# 1-Schematic_LED_PISCA.net
KiCad netlist of a schematic drawn in EasyEDA
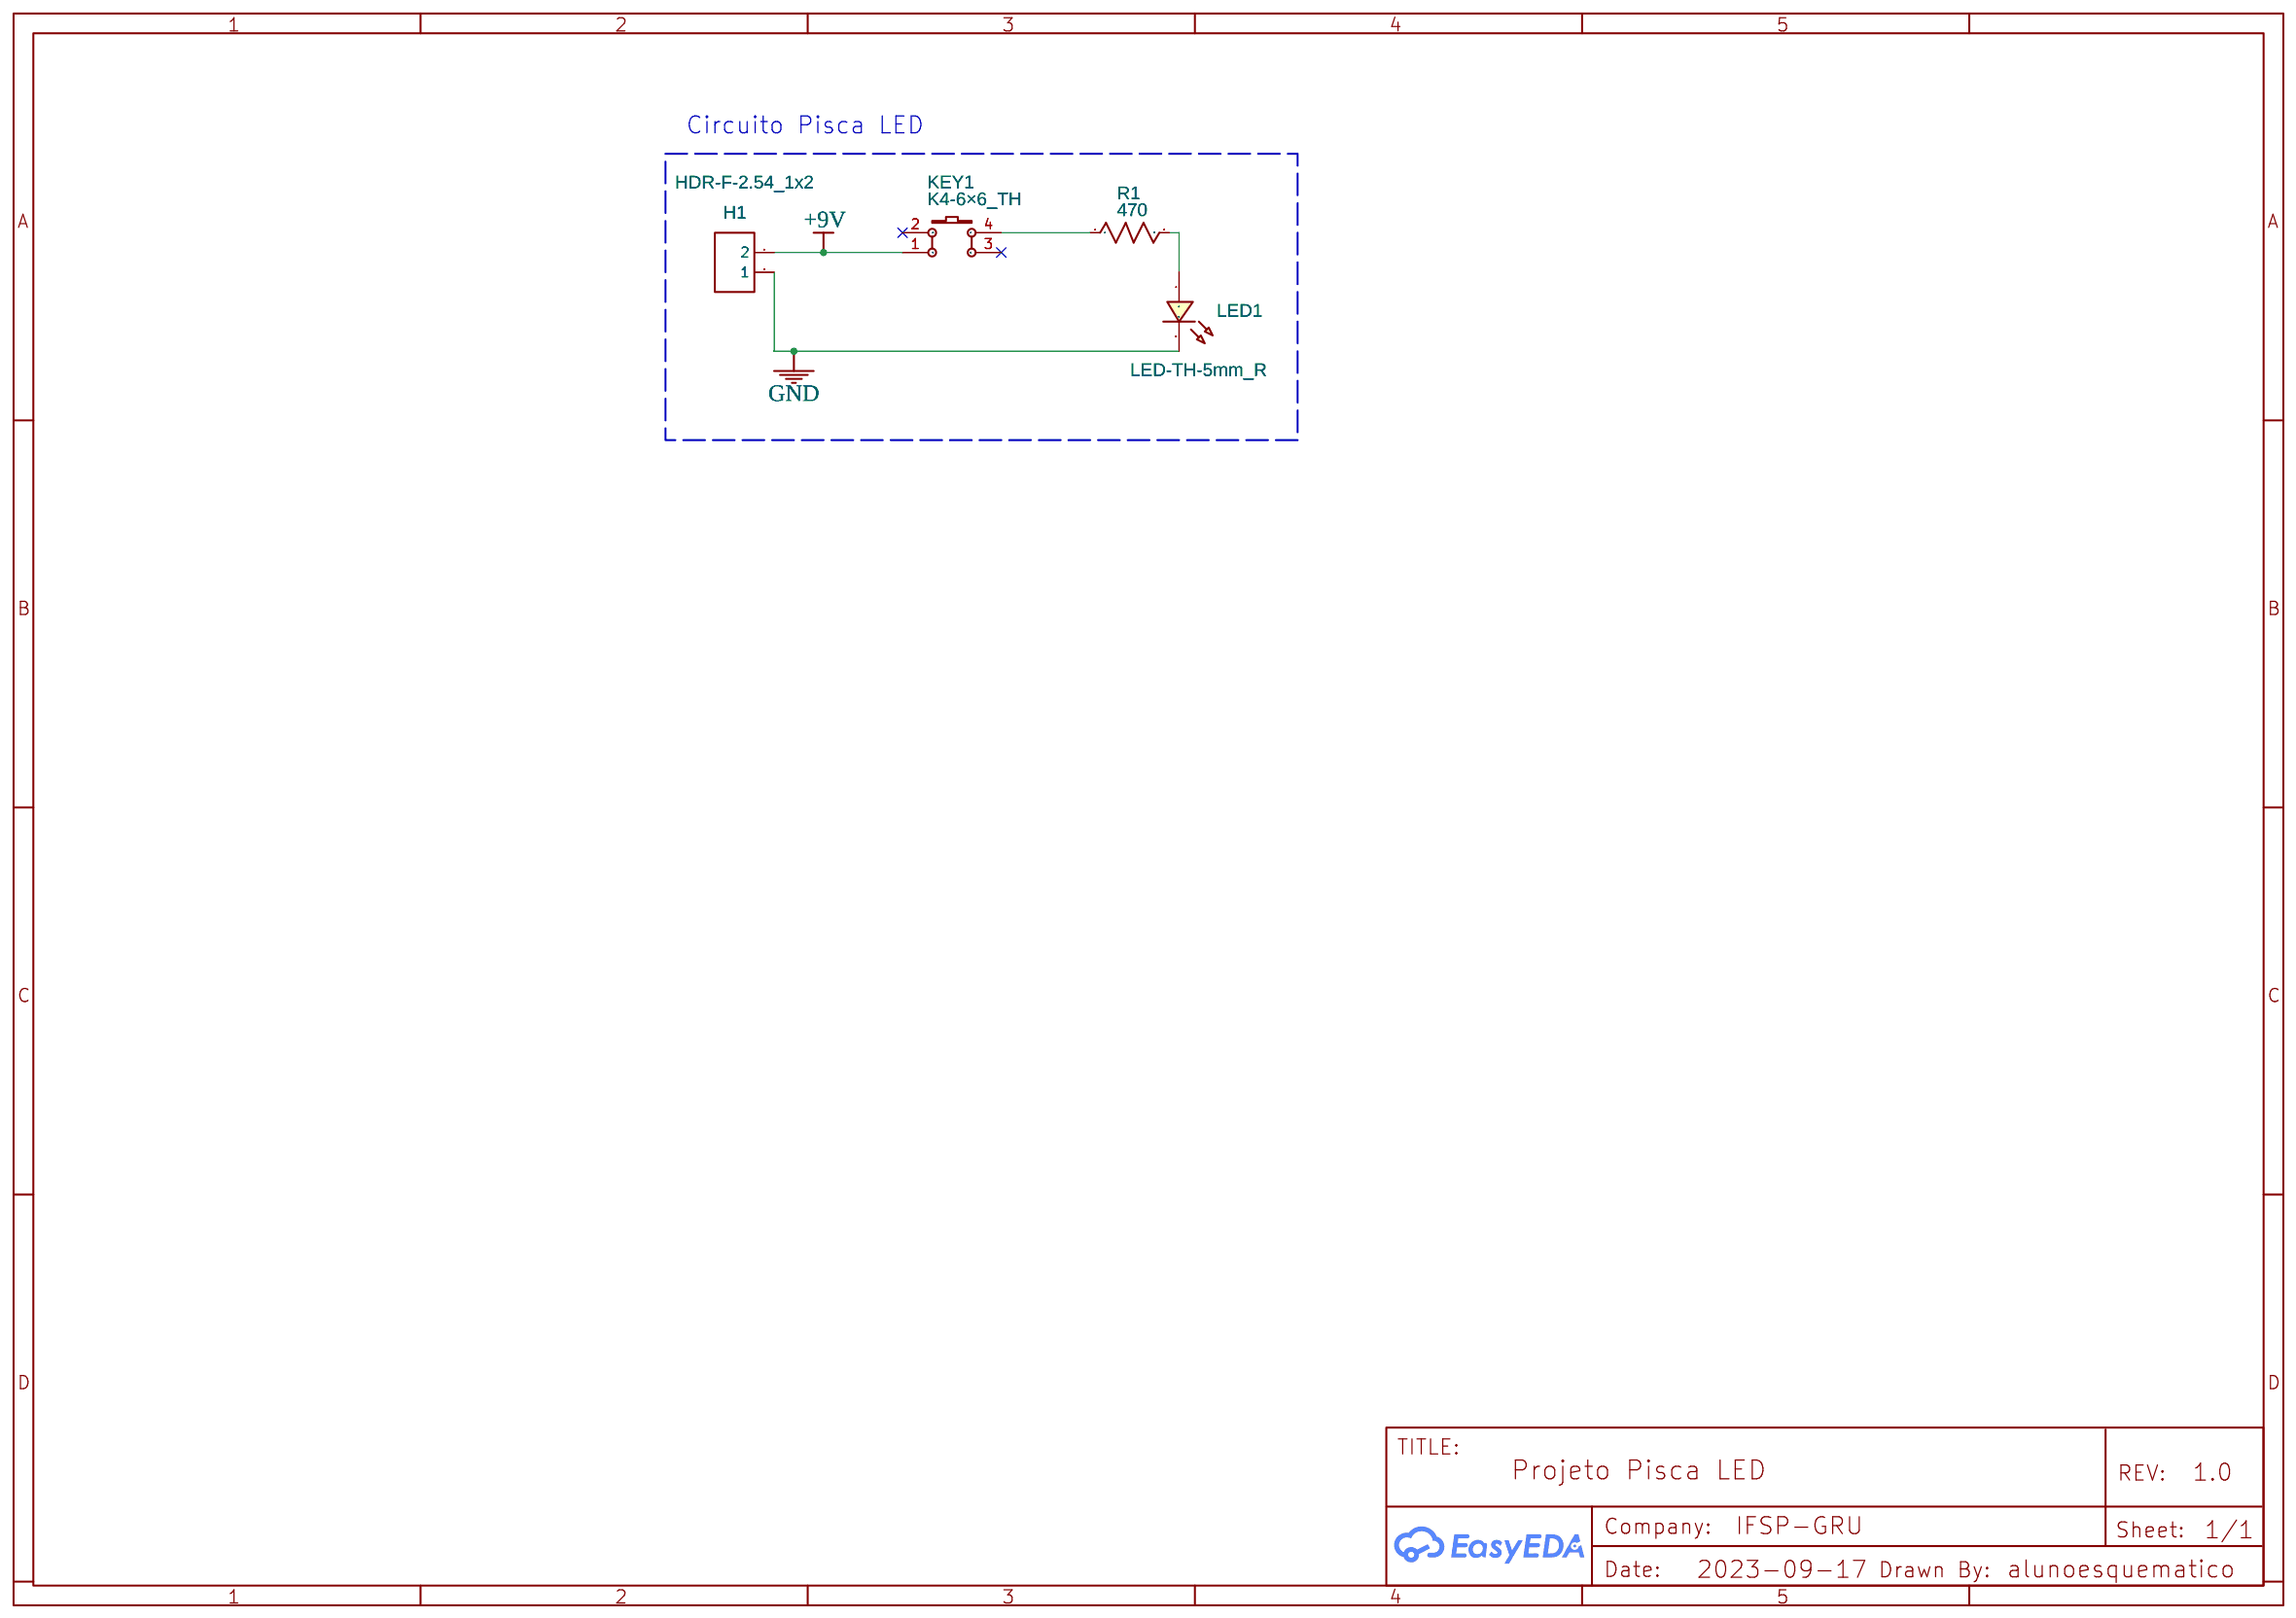
[diagram p0: schematic sheet]

(export (version "E")
  (design (tool "Eeschema 10.0.6"))
  (components
    (comp (ref "H1") (value "HDR-F-2.54_1x2") (libsource (lib "") (part "HDR-F-2.54_1x2")))
    (comp (ref "KEY1")
      (value "K4-6×6_TH")
      (fields (field (name "Manufacturer Part") "K2-1102DP-E4SW-04") (field (name "Manufacturer") "韩国韩荣"))
      (libsource (lib "") (part "K4-6×6_TH"))
    )
    (comp (ref "LED1")
      (value "LED-TH-5mm_R")
      (fields
        (field (name "Manufacturer Part") "333-2SURD/S530-A3")
        (field (name "Manufacturer") "EVERLIGHT(台湾亿光)")
      )
      (libsource (lib "") (part "LED-TH-5mm_R"))
    )
    (comp (ref "R1") (value "470") (libsource (lib "") (part "R_AXIAL-0.4_US")))
  )
  (nets
    (net (code "1") (name "+9V") (class "Default")
      (node (ref "H1") (pin "2") (pinfunction "2_2") (pintype "input"))
      (node (ref "KEY1") (pin "1") (pinfunction "1_1") (pintype "unspecified"))
    )
    (net (code "2") (name "GND") (class "Default")
      (node (ref "H1") (pin "1") (pinfunction "1_1") (pintype "input"))
      (node (ref "LED1") (pin "2") (pinfunction "2_2") (pintype "unspecified"))
    )
    (net (code "3") (name "Net-(KEY1-Pad4)") (class "Default")
      (node (ref "KEY1") (pin "4") (pinfunction "4_4") (pintype "unspecified"))
      (node (ref "R1") (pin "1") (pinfunction "1_1") (pintype "unspecified"))
    )
    (net (code "4") (name "Net-(LED1-Pad1)") (class "Default")
      (node (ref "LED1") (pin "1") (pinfunction "1_1") (pintype "unspecified"))
      (node (ref "R1") (pin "2") (pinfunction "2_2") (pintype "unspecified"))
    )
    (net (code "5") (name "unconnected-(KEY1-Pad2)") (class "Default")
      (node (ref "KEY1") (pin "2") (pinfunction "2_2") (pintype "unspecified+no_connect"))
    )
    (net (code "6") (name "unconnected-(KEY1-Pad3)") (class "Default")
      (node (ref "KEY1") (pin "3") (pinfunction "3_3") (pintype "unspecified+no_connect"))
    )
  )
)
